# Adafruit_tfttouchshield_v2_2.net
KiCad netlist of a schematic drawn in EAGLE
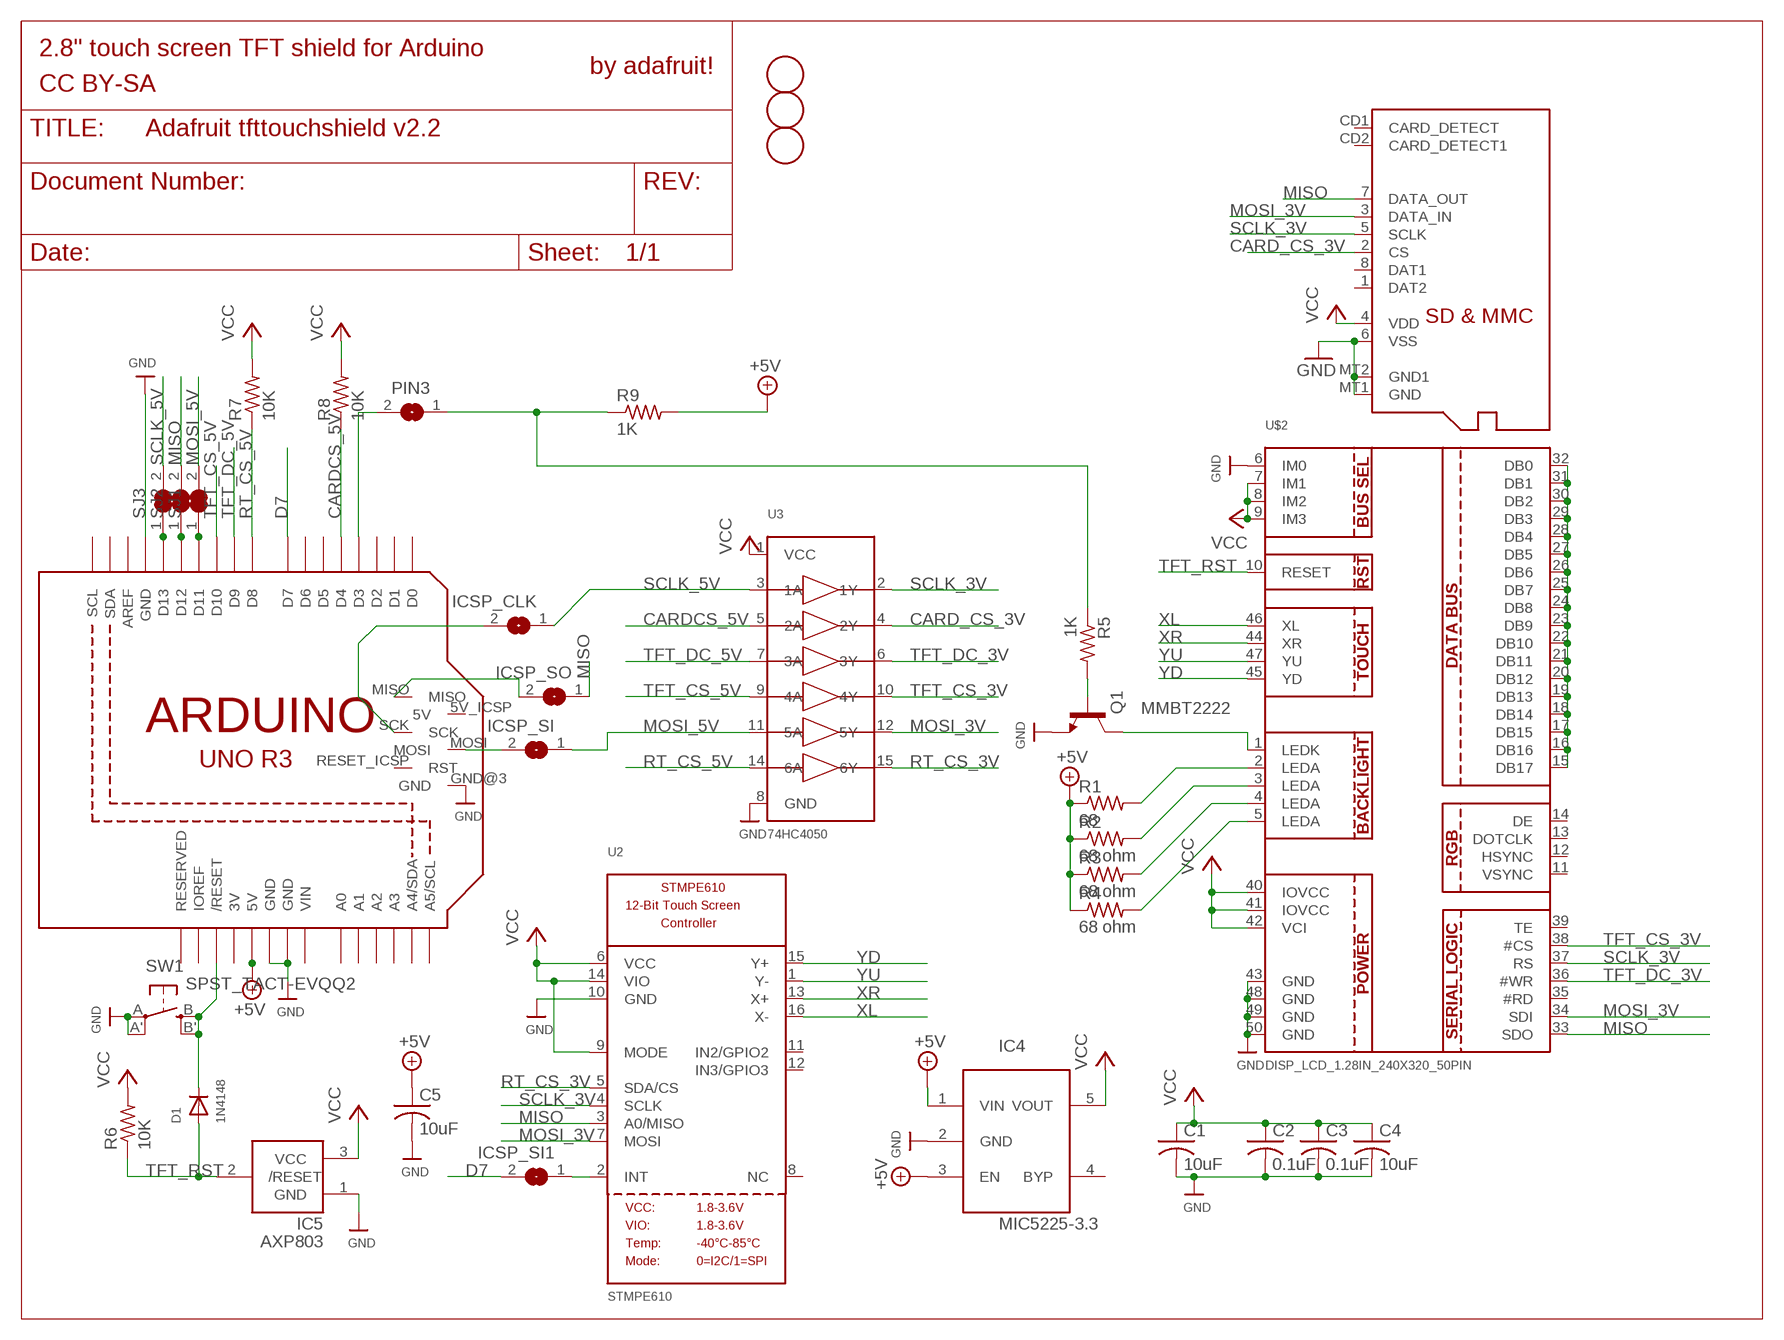
[diagram p0: schematic, sheet 1]

(export (version "E")
  (design (tool "Eeschema 10.0.6"))
  (components
    (comp (ref "C1")
      (value "10uF")
      (footprint "eagle-import:C0805K")
      (libsource (lib "eagle-import") (part "C-USC0805K"))
    )
    (comp (ref "C2")
      (value "0.1uF")
      (footprint "eagle-import:C0805K")
      (libsource (lib "eagle-import") (part "C-USC0805K"))
    )
    (comp (ref "C3")
      (value "0.1uF")
      (footprint "eagle-import:C0805K")
      (libsource (lib "eagle-import") (part "C-USC0805K"))
    )
    (comp (ref "C4")
      (value "10uF")
      (footprint "eagle-import:C0805K")
      (libsource (lib "eagle-import") (part "C-USC0805K"))
    )
    (comp (ref "C5")
      (value "10uF")
      (footprint "eagle-import:C0805K")
      (libsource (lib "eagle-import") (part "C-USC0805K"))
    )
    (comp (ref "D1")
      (value "1N4148")
      (footprint "eagle-import:SOD-323F")
      (libsource (lib "eagle-import") (part "DIODESOD-323F"))
    )
    (comp (ref "IC4")
      (value "MIC5225-3.3")
      (footprint "eagle-import:SOT23-5L")
      (libsource (lib "eagle-import") (part "LP298XS"))
    )
    (comp (ref "IC5")
      (value "AXP803")
      (footprint "eagle-import:SOT23")
      (libsource (lib "eagle-import") (part "AXP083-SAG"))
    )
    (comp (ref "ICSP_CLK")
      (value "SOLDERJUMPERREFLOW_NOPASTE")
      (footprint "eagle-import:SOLDERJUMPER_REFLOW_NOPASTE")
      (libsource (lib "eagle-import") (part "SOLDERJUMPERREFLOW_NOPASTE"))
    )
    (comp (ref "ICSP_SI")
      (value "SOLDERJUMPERREFLOW_NOPASTE")
      (footprint "eagle-import:SOLDERJUMPER_REFLOW_NOPASTE")
      (libsource (lib "eagle-import") (part "SOLDERJUMPERREFLOW_NOPASTE"))
    )
    (comp (ref "ICSP_SI1")
      (value "SOLDERJUMPERREFLOW_NOPASTE")
      (footprint "eagle-import:SOLDERJUMPER_REFLOW_NOPASTE")
      (libsource (lib "eagle-import") (part "SOLDERJUMPERREFLOW_NOPASTE"))
    )
    (comp (ref "ICSP_SO")
      (value "SOLDERJUMPERREFLOW_NOPASTE")
      (footprint "eagle-import:SOLDERJUMPER_REFLOW_NOPASTE")
      (libsource (lib "eagle-import") (part "SOLDERJUMPERREFLOW_NOPASTE"))
    )
    (comp (ref "PIN3")
      (value "SOLDERJUMPERREFLOW_NOPASTE")
      (footprint "eagle-import:SOLDERJUMPER_REFLOW_NOPASTE")
      (libsource (lib "eagle-import") (part "SOLDERJUMPERREFLOW_NOPASTE"))
    )
    (comp (ref "Q1")
      (value "MMBT2222")
      (footprint "eagle-import:SOT23-BEC")
      (libsource (lib "eagle-import") (part "-NPN-SOT23-BECMMBT2222ALT1"))
    )
    (comp (ref "R1")
      (value "68")
      (footprint "eagle-import:R0805")
      (libsource (lib "eagle-import") (part "R-US_R0805"))
    )
    (comp (ref "R2")
      (value "68 ohm")
      (footprint "eagle-import:R0805")
      (libsource (lib "eagle-import") (part "R-US_R0805"))
    )
    (comp (ref "R3")
      (value "68 ohm")
      (footprint "eagle-import:R0805")
      (libsource (lib "eagle-import") (part "R-US_R0805"))
    )
    (comp (ref "R4")
      (value "68 ohm")
      (footprint "eagle-import:R0805")
      (libsource (lib "eagle-import") (part "R-US_R0805"))
    )
    (comp (ref "R5")
      (value "1K")
      (footprint "eagle-import:R0805")
      (libsource (lib "eagle-import") (part "R-US_R0805"))
    )
    (comp (ref "R6")
      (value "10K")
      (footprint "eagle-import:R0805")
      (libsource (lib "eagle-import") (part "R-US_R0805"))
    )
    (comp (ref "R7")
      (value "10K")
      (footprint "eagle-import:R0805")
      (libsource (lib "eagle-import") (part "R-US_R0805"))
    )
    (comp (ref "R8")
      (value "10K")
      (footprint "eagle-import:R0805")
      (libsource (lib "eagle-import") (part "R-US_R0805"))
    )
    (comp (ref "R9")
      (value "1K")
      (footprint "eagle-import:R0805")
      (libsource (lib "eagle-import") (part "R-US_R0805"))
    )
    (comp (ref "SJ1")
      (value "SOLDERJUMPER_CLOSED")
      (footprint "eagle-import:SOLDERJUMPER_CLOSEDWIRE")
      (libsource (lib "eagle-import") (part "SOLDERJUMPER_CLOSED"))
    )
    (comp (ref "SJ2")
      (value "SOLDERJUMPER_CLOSED")
      (footprint "eagle-import:SOLDERJUMPER_CLOSEDWIRE")
      (libsource (lib "eagle-import") (part "SOLDERJUMPER_CLOSED"))
    )
    (comp (ref "SJ3")
      (value "SOLDERJUMPER_CLOSED")
      (footprint "eagle-import:SOLDERJUMPER_CLOSEDWIRE")
      (libsource (lib "eagle-import") (part "SOLDERJUMPER_CLOSED"))
    )
    (comp (ref "SW1")
      (value "SPST_TACT-EVQQ2")
      (footprint "eagle-import:EVQ-Q2")
      (libsource (lib "eagle-import") (part "SPST_TACT-EVQQ2"))
    )
    (comp (ref "U$2")
      (value "DISP_LCD_1.28IN_240X320_50PIN")
      (footprint "eagle-import:TFT_2.83IN_240X320_50PIN")
      (libsource (lib "eagle-import") (part "DISP_LCD_1.28IN_240X320_50PIN"))
    )
    (comp (ref "U$3")
      (value "MICROSD")
      (footprint "eagle-import:MICROSD")
      (libsource (lib "eagle-import") (part "MICROSD"))
    )
    (comp (ref "U$10")
      (value "FIDUCIAL")
      (footprint "eagle-import:FIDUCIAL_1MM")
      (libsource (lib "eagle-import") (part "FIDUCIAL"))
    )
    (comp (ref "U$11")
      (value "FIDUCIAL")
      (footprint "eagle-import:FIDUCIAL_1MM")
      (libsource (lib "eagle-import") (part "FIDUCIAL"))
    )
    (comp (ref "U$17")
      (value "ARDUINO_R3_ICSPSMT")
      (footprint "eagle-import:ARDUINOR3_ICSP_SMT")
      (libsource (lib "eagle-import") (part "ARDUINO_R3_ICSPSMT"))
    )
    (comp (ref "U$19")
      (value "FIDUCIAL")
      (footprint "eagle-import:FIDUCIAL_1MM")
      (libsource (lib "eagle-import") (part "FIDUCIAL"))
    )
    (comp (ref "U2")
      (value "STMPE610")
      (footprint "eagle-import:QFN16_3MM")
      (libsource (lib "eagle-import") (part "STMPE610"))
    )
    (comp (ref "U3")
      (value "74HC4050")
      (footprint "eagle-import:SOIC16")
      (libsource (lib "eagle-import") (part "74HC4050D"))
    )
  )
  (nets
    (net (code "1") (name "+5V") (class "Default")
      (node (ref "C5") (pin "1") (pinfunction "1_1") (pintype "passive"))
      (node (ref "IC4") (pin "1") (pinfunction "VIN_1") (pintype "bidirectional"))
      (node (ref "IC4") (pin "3") (pinfunction "EN_3") (pintype "bidirectional"))
      (node (ref "R1") (pin "1") (pinfunction "1_1") (pintype "passive"))
      (node (ref "R2") (pin "1") (pinfunction "1_1") (pintype "passive"))
      (node (ref "R3") (pin "1") (pinfunction "1_1") (pintype "passive"))
      (node (ref "R4") (pin "1") (pinfunction "1_1") (pintype "passive"))
      (node (ref "R9") (pin "2") (pinfunction "2_2") (pintype "passive"))
      (node (ref "U$17") (pin "5V") (pinfunction "5V_5V") (pintype "power_in"))
    )
    (net (code "2") (name "/3V") (class "Default")
      (node (ref "U$17") (pin "3V") (pinfunction "3V_3V") (pintype "power_in"))
    )
    (net (code "3") (name "/CARDCS_5V") (class "Default")
      (node (ref "R8") (pin "1") (pinfunction "1_1") (pintype "passive"))
      (node (ref "U$17") (pin "D4") (pinfunction "D4_D4") (pintype "bidirectional"))
      (node (ref "U3") (pin "5") (pinfunction "2A_5") (pintype "bidirectional"))
    )
    (net (code "4") (name "/CARD_CS_3V") (class "Default")
      (node (ref "U$3") (pin "2") (pinfunction "CS_2") (pintype "input"))
      (node (ref "U3") (pin "4") (pinfunction "2Y_4") (pintype "bidirectional"))
    )
    (net (code "5") (name "/D7") (class "Default")
      (node (ref "ICSP_SI1") (pin "2") (pinfunction "2_2") (pintype "passive"))
      (node (ref "U$17") (pin "D7") (pinfunction "D7_D7") (pintype "bidirectional"))
    )
    (net (code "6") (name "/MISO") (class "Default")
      (node (ref "ICSP_SO") (pin "1") (pinfunction "1_1") (pintype "passive"))
      (node (ref "SJ2") (pin "2") (pinfunction "2_2") (pintype "passive"))
      (node (ref "U$2") (pin "33") (pinfunction "SDO_33") (pintype "bidirectional"))
      (node (ref "U$3") (pin "7") (pinfunction "DATA_OUT_7") (pintype "output"))
      (node (ref "U2") (pin "3") (pinfunction "A0/MISO_3") (pintype "bidirectional"))
    )
    (net (code "7") (name "/MOSI_3V") (class "Default")
      (node (ref "U$2") (pin "34") (pinfunction "SDI_34") (pintype "bidirectional"))
      (node (ref "U$3") (pin "3") (pinfunction "DATA_IN_3") (pintype "input"))
      (node (ref "U2") (pin "7") (pinfunction "MOSI_7") (pintype "input"))
      (node (ref "U3") (pin "12") (pinfunction "5Y_12") (pintype "bidirectional"))
    )
    (net (code "8") (name "/MOSI_5V") (class "Default")
      (node (ref "ICSP_SI") (pin "1") (pinfunction "1_1") (pintype "passive"))
      (node (ref "SJ1") (pin "2") (pinfunction "2_2") (pintype "passive"))
      (node (ref "U3") (pin "11") (pinfunction "5A_11") (pintype "bidirectional"))
    )
    (net (code "9") (name "/RT_CS_3V") (class "Default")
      (node (ref "U2") (pin "5") (pinfunction "SDA/CS_5") (pintype "bidirectional"))
      (node (ref "U3") (pin "15") (pinfunction "6Y_15") (pintype "bidirectional"))
    )
    (net (code "10") (name "/RT_CS_5V") (class "Default")
      (node (ref "R7") (pin "1") (pinfunction "1_1") (pintype "passive"))
      (node (ref "U$17") (pin "D8") (pinfunction "D8_D8") (pintype "bidirectional"))
      (node (ref "U3") (pin "14") (pinfunction "6A_14") (pintype "bidirectional"))
    )
    (net (code "11") (name "/SCLK_3V") (class "Default")
      (node (ref "U$2") (pin "37") (pinfunction "RS_37") (pintype "bidirectional"))
      (node (ref "U$3") (pin "5") (pinfunction "SCLK_5") (pintype "input"))
      (node (ref "U2") (pin "4") (pinfunction "SCLK_4") (pintype "bidirectional"))
      (node (ref "U3") (pin "2") (pinfunction "1Y_2") (pintype "bidirectional"))
    )
    (net (code "12") (name "/SCLK_5V") (class "Default")
      (node (ref "ICSP_CLK") (pin "1") (pinfunction "1_1") (pintype "passive"))
      (node (ref "SJ3") (pin "2") (pinfunction "2_2") (pintype "passive"))
      (node (ref "U3") (pin "3") (pinfunction "1A_3") (pintype "bidirectional"))
    )
    (net (code "13") (name "/TFT_CS_3V") (class "Default")
      (node (ref "U$2") (pin "38") (pinfunction "#CS_38") (pintype "bidirectional"))
      (node (ref "U3") (pin "10") (pinfunction "4Y_10") (pintype "bidirectional"))
    )
    (net (code "14") (name "/TFT_CS_5V") (class "Default")
      (node (ref "U$17") (pin "D10") (pinfunction "D10_D10") (pintype "bidirectional"))
      (node (ref "U3") (pin "9") (pinfunction "4A_9") (pintype "bidirectional"))
    )
    (net (code "15") (name "/TFT_DC_3V") (class "Default")
      (node (ref "U$2") (pin "36") (pinfunction "#WR_36") (pintype "bidirectional"))
      (node (ref "U3") (pin "6") (pinfunction "3Y_6") (pintype "bidirectional"))
    )
    (net (code "16") (name "/TFT_DC_5V") (class "Default")
      (node (ref "U$17") (pin "D9") (pinfunction "D9_D9") (pintype "bidirectional"))
      (node (ref "U3") (pin "7") (pinfunction "3A_7") (pintype "bidirectional"))
    )
    (net (code "17") (name "/TFT_RST") (class "Default")
      (node (ref "D1") (pin "A") (pinfunction "A_A") (pintype "passive"))
      (node (ref "IC5") (pin "2") (pinfunction "/RESET_2") (pintype "output"))
      (node (ref "R6") (pin "1") (pinfunction "1_1") (pintype "passive"))
      (node (ref "U$2") (pin "10") (pinfunction "RESET_10") (pintype "bidirectional"))
    )
    (net (code "18") (name "/VIN") (class "Default")
      (node (ref "U$17") (pin "VIN") (pinfunction "VIN_VIN") (pintype "power_in"))
    )
    (net (code "19") (name "/XL") (class "Default")
      (node (ref "U$2") (pin "46") (pinfunction "XL_46") (pintype "bidirectional"))
      (node (ref "U2") (pin "16") (pinfunction "X-_16") (pintype "input"))
    )
    (net (code "20") (name "/XR") (class "Default")
      (node (ref "U$2") (pin "44") (pinfunction "XR_44") (pintype "bidirectional"))
      (node (ref "U2") (pin "13") (pinfunction "X+_13") (pintype "input"))
    )
    (net (code "21") (name "/YD") (class "Default")
      (node (ref "U$2") (pin "45") (pinfunction "YD_45") (pintype "bidirectional"))
      (node (ref "U2") (pin "15") (pinfunction "Y+_15") (pintype "input"))
    )
    (net (code "22") (name "/YU") (class "Default")
      (node (ref "U$2") (pin "47") (pinfunction "YU_47") (pintype "bidirectional"))
      (node (ref "U2") (pin "1") (pinfunction "Y-_1") (pintype "input"))
    )
    (net (code "23") (name "GND") (class "Default")
      (node (ref "C1") (pin "2") (pinfunction "2_2") (pintype "passive"))
      (node (ref "C2") (pin "2") (pinfunction "2_2") (pintype "passive"))
      (node (ref "C3") (pin "2") (pinfunction "2_2") (pintype "passive"))
      (node (ref "C4") (pin "2") (pinfunction "2_2") (pintype "passive"))
      (node (ref "C5") (pin "2") (pinfunction "2_2") (pintype "passive"))
      (node (ref "IC4") (pin "2") (pinfunction "GND_2") (pintype "bidirectional"))
      (node (ref "IC5") (pin "1") (pinfunction "GND_1") (pintype "power_in"))
      (node (ref "Q1") (pin "E") (pinfunction "E_E") (pintype "passive"))
      (node (ref "SW1") (pin "A") (pinfunction "P_A") (pintype "passive"))
      (node (ref "SW1") (pin "A'") (pinfunction "P1_A'") (pintype "passive"))
      (node (ref "U$17") (pin "GND") (pinfunction "GND_GND") (pintype "power_in"))
      (node (ref "U$17") (pin "GND@1") (pinfunction "GND_GND@1") (pintype "power_in"))
      (node (ref "U$17") (pin "GND@2") (pinfunction "GND_GND@2") (pintype "power_in"))
      (node (ref "U$17") (pin "GND@3") (pinfunction "GND_GND@3") (pintype "passive"))
      (node (ref "U$2") (pin "43") (pinfunction "GND_43") (pintype "bidirectional"))
      (node (ref "U$2") (pin "48") (pinfunction "GND_48") (pintype "bidirectional"))
      (node (ref "U$2") (pin "49") (pinfunction "GND_49") (pintype "bidirectional"))
      (node (ref "U$2") (pin "50") (pinfunction "GND_50") (pintype "bidirectional"))
      (node (ref "U$2") (pin "6") (pinfunction "IM0_6") (pintype "bidirectional"))
      (node (ref "U$3") (pin "6") (pinfunction "VSS_6") (pintype "power_in"))
      (node (ref "U$3") (pin "MT1") (pinfunction "GND_MT1") (pintype "power_in"))
      (node (ref "U$3") (pin "MT2") (pinfunction "GND1_MT2") (pintype "power_in"))
      (node (ref "U2") (pin "10") (pinfunction "GND_10") (pintype "power_in"))
      (node (ref "U3") (pin "8") (pinfunction "GND_8") (pintype "bidirectional"))
    )
    (net (code "24") (name "Net-(ICSP_CLK-Pad2)") (class "Default")
      (node (ref "ICSP_CLK") (pin "2") (pinfunction "2_2") (pintype "passive"))
      (node (ref "U$17") (pin "SCK") (pinfunction "SCK_SCK") (pintype "passive"))
    )
    (net (code "25") (name "Net-(ICSP_SI-Pad2)") (class "Default")
      (node (ref "ICSP_SI") (pin "2") (pinfunction "2_2") (pintype "passive"))
      (node (ref "U$17") (pin "MOSI") (pinfunction "MOSI_MOSI") (pintype "passive"))
    )
    (net (code "26") (name "Net-(ICSP_SO-Pad2)") (class "Default")
      (node (ref "ICSP_SO") (pin "2") (pinfunction "2_2") (pintype "passive"))
      (node (ref "U$17") (pin "MISO") (pinfunction "MISO_MISO") (pintype "passive"))
    )
    (net (code "27") (name "Net-(PIN3-Pad1)") (class "Default")
      (node (ref "PIN3") (pin "1") (pinfunction "1_1") (pintype "passive"))
      (node (ref "R5") (pin "1") (pinfunction "1_1") (pintype "passive"))
      (node (ref "R9") (pin "1") (pinfunction "1_1") (pintype "passive"))
    )
    (net (code "28") (name "Net-(PIN3-Pad2)") (class "Default")
      (node (ref "PIN3") (pin "2") (pinfunction "2_2") (pintype "passive"))
      (node (ref "U$17") (pin "D3") (pinfunction "D3_D3") (pintype "bidirectional"))
    )
    (net (code "29") (name "Net-(Q1-PadB)") (class "Default")
      (node (ref "Q1") (pin "B") (pinfunction "B_B") (pintype "passive"))
      (node (ref "R5") (pin "2") (pinfunction "2_2") (pintype "passive"))
    )
    (net (code "30") (name "Net-(R1-Pad2)") (class "Default")
      (node (ref "R1") (pin "2") (pinfunction "2_2") (pintype "passive"))
      (node (ref "U$2") (pin "2") (pinfunction "LEDA_2") (pintype "bidirectional"))
    )
    (net (code "31") (name "Net-(R2-Pad2)") (class "Default")
      (node (ref "R2") (pin "2") (pinfunction "2_2") (pintype "passive"))
      (node (ref "U$2") (pin "3") (pinfunction "LEDA_3") (pintype "bidirectional"))
    )
    (net (code "32") (name "Net-(R3-Pad2)") (class "Default")
      (node (ref "R3") (pin "2") (pinfunction "2_2") (pintype "passive"))
      (node (ref "U$2") (pin "4") (pinfunction "LEDA_4") (pintype "bidirectional"))
    )
    (net (code "33") (name "Net-(R4-Pad2)") (class "Default")
      (node (ref "R4") (pin "2") (pinfunction "2_2") (pintype "passive"))
      (node (ref "U$2") (pin "5") (pinfunction "LEDA_5") (pintype "bidirectional"))
    )
    (net (code "34") (name "Net-(SJ1-Pad1)") (class "Default")
      (node (ref "SJ1") (pin "1") (pinfunction "1_1") (pintype "passive"))
      (node (ref "U$17") (pin "D11") (pinfunction "D11_D11") (pintype "bidirectional"))
    )
    (net (code "35") (name "Net-(SJ2-Pad1)") (class "Default")
      (node (ref "SJ2") (pin "1") (pinfunction "1_1") (pintype "passive"))
      (node (ref "U$17") (pin "D12") (pinfunction "D12_D12") (pintype "bidirectional"))
    )
    (net (code "36") (name "Net-(SJ3-Pad1)") (class "Default")
      (node (ref "SJ3") (pin "1") (pinfunction "1_1") (pintype "passive"))
      (node (ref "U$17") (pin "D13") (pinfunction "D13_D13") (pintype "bidirectional"))
    )
    (net (code "37") (name "Net-(SW1-S)") (class "Default")
      (node (ref "D1") (pin "C") (pinfunction "C_C") (pintype "passive"))
      (node (ref "SW1") (pin "B") (pinfunction "S_B") (pintype "passive"))
      (node (ref "SW1") (pin "B'") (pinfunction "S1_B'") (pintype "passive"))
      (node (ref "U$17") (pin "RESET") (pinfunction "/RESET_RESET") (pintype "bidirectional"))
    )
    (net (code "38") (name "Net-(U$2-DB0)") (class "Default")
      (node (ref "U$2") (pin "15") (pinfunction "DB17_15") (pintype "bidirectional"))
      (node (ref "U$2") (pin "16") (pinfunction "DB16_16") (pintype "bidirectional"))
      (node (ref "U$2") (pin "17") (pinfunction "DB15_17") (pintype "bidirectional"))
      (node (ref "U$2") (pin "18") (pinfunction "DB14_18") (pintype "bidirectional"))
      (node (ref "U$2") (pin "19") (pinfunction "DB13_19") (pintype "bidirectional"))
      (node (ref "U$2") (pin "20") (pinfunction "DB12_20") (pintype "bidirectional"))
      (node (ref "U$2") (pin "21") (pinfunction "DB11_21") (pintype "bidirectional"))
      (node (ref "U$2") (pin "22") (pinfunction "DB10_22") (pintype "bidirectional"))
      (node (ref "U$2") (pin "23") (pinfunction "DB9_23") (pintype "bidirectional"))
      (node (ref "U$2") (pin "24") (pinfunction "DB8_24") (pintype "bidirectional"))
      (node (ref "U$2") (pin "25") (pinfunction "DB7_25") (pintype "bidirectional"))
      (node (ref "U$2") (pin "26") (pinfunction "DB6_26") (pintype "bidirectional"))
      (node (ref "U$2") (pin "27") (pinfunction "DB5_27") (pintype "bidirectional"))
      (node (ref "U$2") (pin "28") (pinfunction "DB4_28") (pintype "bidirectional"))
      (node (ref "U$2") (pin "29") (pinfunction "DB3_29") (pintype "bidirectional"))
      (node (ref "U$2") (pin "30") (pinfunction "DB2_30") (pintype "bidirectional"))
      (node (ref "U$2") (pin "31") (pinfunction "DB1_31") (pintype "bidirectional"))
      (node (ref "U$2") (pin "32") (pinfunction "DB0_32") (pintype "bidirectional"))
    )
    (net (code "39") (name "Net-(U$2-LEDK)") (class "Default")
      (node (ref "Q1") (pin "C") (pinfunction "C_C") (pintype "passive"))
      (node (ref "U$2") (pin "1") (pinfunction "LEDK_1") (pintype "bidirectional"))
    )
    (net (code "40") (name "Net-(U2-INT)") (class "Default")
      (node (ref "ICSP_SI1") (pin "1") (pinfunction "1_1") (pintype "passive"))
      (node (ref "U2") (pin "2") (pinfunction "INT_2") (pintype "output"))
    )
    (net (code "41") (name "VCC") (class "Default")
      (node (ref "C1") (pin "1") (pinfunction "1_1") (pintype "passive"))
      (node (ref "C2") (pin "1") (pinfunction "1_1") (pintype "passive"))
      (node (ref "C3") (pin "1") (pinfunction "1_1") (pintype "passive"))
      (node (ref "C4") (pin "1") (pinfunction "1_1") (pintype "passive"))
      (node (ref "IC4") (pin "5") (pinfunction "VOUT_5") (pintype "bidirectional"))
      (node (ref "IC5") (pin "3") (pinfunction "VCC_3") (pintype "power_in"))
      (node (ref "R6") (pin "2") (pinfunction "2_2") (pintype "passive"))
      (node (ref "R7") (pin "2") (pinfunction "2_2") (pintype "passive"))
      (node (ref "R8") (pin "2") (pinfunction "2_2") (pintype "passive"))
      (node (ref "U$2") (pin "40") (pinfunction "IOVCC_40") (pintype "bidirectional"))
      (node (ref "U$2") (pin "41") (pinfunction "IOVCC_41") (pintype "bidirectional"))
      (node (ref "U$2") (pin "42") (pinfunction "VCI_42") (pintype "bidirectional"))
      (node (ref "U$2") (pin "7") (pinfunction "IM1_7") (pintype "bidirectional"))
      (node (ref "U$2") (pin "8") (pinfunction "IM2_8") (pintype "bidirectional"))
      (node (ref "U$2") (pin "9") (pinfunction "IM3_9") (pintype "bidirectional"))
      (node (ref "U$3") (pin "4") (pinfunction "VDD_4") (pintype "power_in"))
      (node (ref "U2") (pin "14") (pinfunction "VIO_14") (pintype "power_in"))
      (node (ref "U2") (pin "6") (pinfunction "VCC_6") (pintype "power_in"))
      (node (ref "U2") (pin "9") (pinfunction "MODE_9") (pintype "input"))
      (node (ref "U3") (pin "1") (pinfunction "VCC_1") (pintype "bidirectional"))
    )
    (net (code "42") (name "unconnected-(IC4-BYP-Pad4)") (class "Default")
      (node (ref "IC4") (pin "4") (pinfunction "BYP_4") (pintype "bidirectional"))
    )
    (net (code "43") (name "unconnected-(U$2-#RD-Pad35)") (class "Default")
      (node (ref "U$2") (pin "35") (pinfunction "#RD_35") (pintype "bidirectional"))
    )
    (net (code "44") (name "unconnected-(U$2-DE-Pad14)") (class "Default")
      (node (ref "U$2") (pin "14") (pinfunction "DE_14") (pintype "bidirectional"))
    )
    (net (code "45") (name "unconnected-(U$2-DOTCLK-Pad13)") (class "Default")
      (node (ref "U$2") (pin "13") (pinfunction "DOTCLK_13") (pintype "bidirectional"))
    )
    (net (code "46") (name "unconnected-(U$2-HSYNC-Pad12)") (class "Default")
      (node (ref "U$2") (pin "12") (pinfunction "HSYNC_12") (pintype "bidirectional"))
    )
    (net (code "47") (name "unconnected-(U$2-TE-Pad39)") (class "Default")
      (node (ref "U$2") (pin "39") (pinfunction "TE_39") (pintype "bidirectional"))
    )
    (net (code "48") (name "unconnected-(U$2-VSYNC-Pad11)") (class "Default")
      (node (ref "U$2") (pin "11") (pinfunction "VSYNC_11") (pintype "bidirectional"))
    )
    (net (code "49") (name "unconnected-(U$3-CARD_DETECT-PadCD1)") (class "Default")
      (node (ref "U$3") (pin "CD1") (pinfunction "CARD_DETECT_CD1") (pintype "passive"))
    )
    (net (code "50") (name "unconnected-(U$3-CARD_DETECT1-PadCD2)") (class "Default")
      (node (ref "U$3") (pin "CD2") (pinfunction "CARD_DETECT1_CD2") (pintype "passive"))
    )
    (net (code "51") (name "unconnected-(U$3-DAT1-Pad8)") (class "Default")
      (node (ref "U$3") (pin "8") (pinfunction "DAT1_8") (pintype "bidirectional"))
    )
    (net (code "52") (name "unconnected-(U$3-DAT2-Pad1)") (class "Default")
      (node (ref "U$3") (pin "1") (pinfunction "DAT2_1") (pintype "bidirectional"))
    )
    (net (code "53") (name "unconnected-(U$17-5V-Pad5V_ICSP)") (class "Default")
      (node (ref "U$17") (pin "5V_ICSP") (pinfunction "5V_5V_ICSP") (pintype "passive"))
    )
    (net (code "54") (name "unconnected-(U$17-A4{slash}SDA-PadA4)") (class "Default")
      (node (ref "U$17") (pin "A4") (pinfunction "A4/SDA_A4") (pintype "bidirectional"))
    )
    (net (code "55") (name "unconnected-(U$17-A5{slash}SCL-PadA5)") (class "Default")
      (node (ref "U$17") (pin "A5") (pinfunction "A5/SCL_A5") (pintype "bidirectional"))
    )
    (net (code "56") (name "unconnected-(U$17-PadA0)") (class "Default")
      (node (ref "U$17") (pin "A0") (pinfunction "A0_A0") (pintype "bidirectional"))
    )
    (net (code "57") (name "unconnected-(U$17-PadA1)") (class "Default")
      (node (ref "U$17") (pin "A1") (pinfunction "A1_A1") (pintype "bidirectional"))
    )
    (net (code "58") (name "unconnected-(U$17-PadA2)") (class "Default")
      (node (ref "U$17") (pin "A2") (pinfunction "A2_A2") (pintype "bidirectional"))
    )
    (net (code "59") (name "unconnected-(U$17-PadA3)") (class "Default")
      (node (ref "U$17") (pin "A3") (pinfunction "A3_A3") (pintype "bidirectional"))
    )
    (net (code "60") (name "unconnected-(U$17-PadAREF)") (class "Default")
      (node (ref "U$17") (pin "AREF") (pinfunction "AREF_AREF") (pintype "bidirectional"))
    )
    (net (code "61") (name "unconnected-(U$17-PadD0)") (class "Default")
      (node (ref "U$17") (pin "D0") (pinfunction "D0_D0") (pintype "bidirectional"))
    )
    (net (code "62") (name "unconnected-(U$17-PadD1)") (class "Default")
      (node (ref "U$17") (pin "D1") (pinfunction "D1_D1") (pintype "bidirectional"))
    )
    (net (code "63") (name "unconnected-(U$17-PadD2)") (class "Default")
      (node (ref "U$17") (pin "D2") (pinfunction "D2_D2") (pintype "bidirectional"))
    )
    (net (code "64") (name "unconnected-(U$17-PadD5)") (class "Default")
      (node (ref "U$17") (pin "D5") (pinfunction "D5_D5") (pintype "bidirectional"))
    )
    (net (code "65") (name "unconnected-(U$17-PadD6)") (class "Default")
      (node (ref "U$17") (pin "D6") (pinfunction "D6_D6") (pintype "bidirectional"))
    )
    (net (code "66") (name "unconnected-(U$17-PadIOREF)") (class "Default")
      (node (ref "U$17") (pin "IOREF") (pinfunction "IOREF_IOREF") (pintype "output"))
    )
    (net (code "67") (name "unconnected-(U$17-PadRESERVED)") (class "Default")
      (node (ref "U$17") (pin "RESERVED") (pinfunction "RESERVED_RESERVED") (pintype "no_connect"))
    )
    (net (code "68") (name "unconnected-(U$17-PadSCL)") (class "Default")
      (node (ref "U$17") (pin "SCL") (pinfunction "SCL_SCL") (pintype "bidirectional"))
    )
    (net (code "69") (name "unconnected-(U$17-PadSDA)") (class "Default")
      (node (ref "U$17") (pin "SDA") (pinfunction "SDA_SDA") (pintype "bidirectional"))
    )
    (net (code "70") (name "unconnected-(U$17-RST-PadRESET_ICSP)") (class "Default")
      (node (ref "U$17") (pin "RESET_ICSP") (pinfunction "RST_RESET_ICSP") (pintype "passive"))
    )
    (net (code "71") (name "unconnected-(U2-IN2{slash}GPIO2-Pad11)") (class "Default")
      (node (ref "U2") (pin "11") (pinfunction "IN2/GPIO2_11") (pintype "bidirectional"))
    )
    (net (code "72") (name "unconnected-(U2-IN3{slash}GPIO3-Pad12)") (class "Default")
      (node (ref "U2") (pin "12") (pinfunction "IN3/GPIO3_12") (pintype "bidirectional"))
    )
    (net (code "73") (name "unconnected-(U2-NC-Pad8)") (class "Default")
      (node (ref "U2") (pin "8") (pinfunction "NC_8") (pintype "no_connect"))
    )
  )
)
